# TRNG_ying.net
KiCad netlist of a schematic drawn in Altium Designer
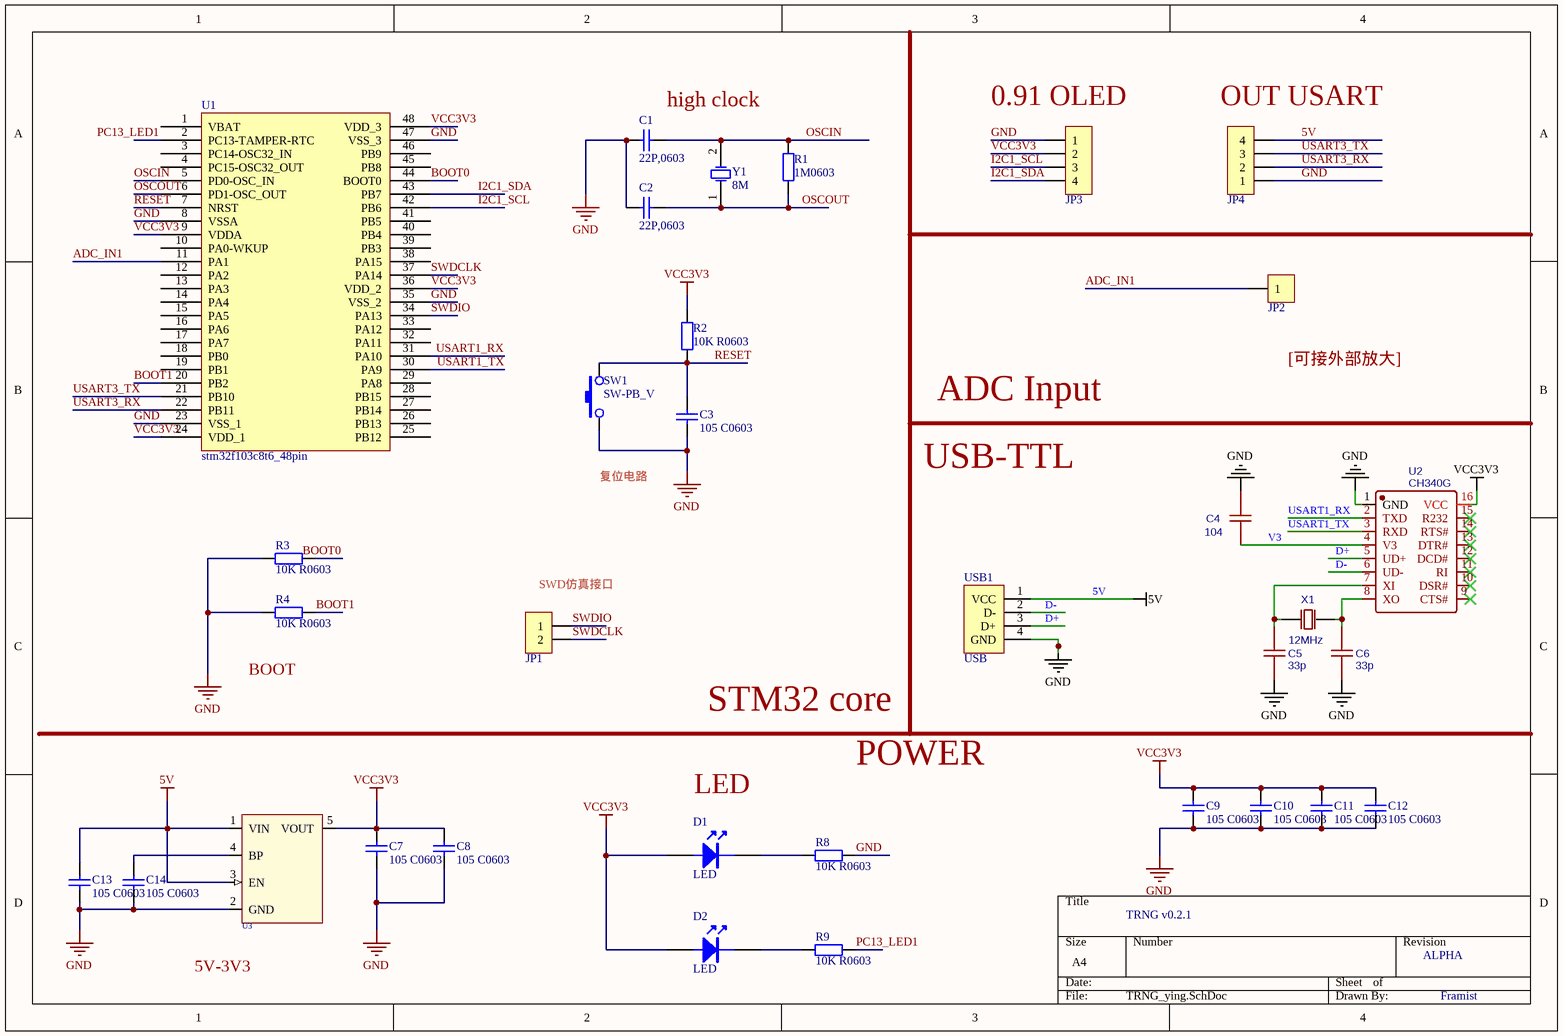
[diagram p0: TRNG_ying.SchDoc]

(export (version "E")
  (design (tool "Eeschema 10.0.6"))
  (components
    (comp (ref "C1")
      (value "22P,0603")
      (footprint "C 0603")
      (description "Capacitor")
      (fields (field (name "PUBLISHER") "Altium Limited"))
      (libsource (lib "STM32F103C8T6") (part "Cap"))
    )
    (comp (ref "C2")
      (value "22P,0603")
      (footprint "C 0603")
      (description "Capacitor")
      (fields (field (name "PUBLISHER") "Altium Limited"))
      (libsource (lib "STM32F103C8T6") (part "Cap"))
    )
    (comp (ref "C3")
      (value "105 C0603")
      (footprint "C 0603")
      (fields (field (name "PUBLISHER") "Altium Limited"))
      (libsource (lib "stm32原理图库") (part "Cap"))
    )
    (comp (ref "C4")
      (value "104")
      (footprint "C 0603")
      (fields
        (field (name "BOM_SUPPLIER PART") "C472790")
        (field (name "BOM_MANUFACTURER PART") "CL10C330JC81PNC")
        (field (name "CONTRIBUTOR") "LCSC")
      )
      (libsource (lib "altium-import") (part "root_1_104_"))
    )
    (comp (ref "C5")
      (value "33p")
      (footprint "C 0603")
      (fields
        (field (name "BOM_SUPPLIER PART") "C472790")
        (field (name "BOM_MANUFACTURER PART") "CL10C330JC81PNC")
        (field (name "CONTRIBUTOR") "LCSC")
      )
      (libsource (lib "altium-import") (part "root_1_33p_"))
    )
    (comp (ref "C6")
      (value "33p")
      (footprint "C 0603")
      (fields
        (field (name "BOM_SUPPLIER PART") "C472790")
        (field (name "BOM_MANUFACTURER PART") "CL10C330JC81PNC")
        (field (name "CONTRIBUTOR") "LCSC")
      )
      (libsource (lib "altium-import") (part "root_1_33p_"))
    )
    (comp (ref "C7")
      (value "105 C0603")
      (footprint "C 0603")
      (fields (field (name "PUBLISHER") "Altium Limited"))
      (libsource (lib "stm32原理图库") (part "Cap"))
    )
    (comp (ref "C8")
      (value "105 C0603")
      (footprint "C 0603")
      (fields (field (name "PUBLISHER") "Altium Limited"))
      (libsource (lib "stm32原理图库") (part "Cap"))
    )
    (comp (ref "C9")
      (value "105 C0603")
      (footprint "C 0603")
      (fields (field (name "PUBLISHER") "Altium Limited"))
      (libsource (lib "stm32原理图库") (part "Cap"))
    )
    (comp (ref "C10")
      (value "105 C0603")
      (footprint "C 0603")
      (fields (field (name "PUBLISHER") "Altium Limited"))
      (libsource (lib "stm32原理图库") (part "Cap"))
    )
    (comp (ref "C11")
      (value "105 C0603")
      (footprint "C 0603")
      (fields (field (name "PUBLISHER") "Altium Limited"))
      (libsource (lib "stm32原理图库") (part "Cap"))
    )
    (comp (ref "C12")
      (value "105 C0603")
      (footprint "C 0603")
      (fields (field (name "PUBLISHER") "Altium Limited"))
      (libsource (lib "stm32原理图库") (part "Cap"))
    )
    (comp (ref "C13")
      (value "105 C0603")
      (footprint "C 0603")
      (fields (field (name "PUBLISHER") "Altium Limited"))
      (libsource (lib "stm32原理图库") (part "Cap"))
    )
    (comp (ref "C14")
      (value "105 C0603")
      (footprint "C 0603")
      (fields (field (name "PUBLISHER") "Altium Limited"))
      (libsource (lib "stm32原理图库") (part "Cap"))
    )
    (comp (ref "D1") (value "LED") (footprint "LED 0805G") (libsource (lib "stm32原理图库") (part "LED")))
    (comp (ref "D2") (value "LED") (footprint "LED 0805G") (libsource (lib "stm32原理图库") (part "LED")))
    (comp (ref "JP1")
      (value "HDR-1X2")
      (footprint "HDR-1X2")
      (description "2P接插件")
      (fields (field (name "版权归属") "源创客"))
      (libsource (lib "接插件") (part "Header 2"))
    )
    (comp (ref "JP2")
      (value "HDR-1X1")
      (footprint "HDR-1X1")
      (description "1P接插件")
      (fields (field (name "版权归属") "源创客"))
      (libsource (lib "接插件") (part "Header 1"))
    )
    (comp (ref "JP3")
      (value "HDR-1X4")
      (footprint "HDR-1X4")
      (description "4P接插件")
      (fields (field (name "版权归属") "源创客"))
      (libsource (lib "接插件") (part "Header 4"))
    )
    (comp (ref "JP4")
      (value "HDR-1X4")
      (footprint "HDR-1X4")
      (description "4P接插件")
      (fields (field (name "版权归属") "源创客"))
      (libsource (lib "") (part "Header 4_1"))
    )
    (comp (ref "R1")
      (value "1M0603")
      (footprint "R 0603")
      (description "Resistor")
      (fields (field (name "PUBLISHER") "Altium Limited"))
      (libsource (lib "STM32F103C8T6") (part "Res2"))
    )
    (comp (ref "R2")
      (value "10K R0603")
      (footprint "R 0603")
      (fields (field (name "PUBLISHER") "Altium Limited"))
      (libsource (lib "") (part "Res2_1"))
    )
    (comp (ref "R3")
      (value "10K R0603")
      (footprint "R 0603")
      (fields (field (name "PUBLISHER") "Altium Limited"))
      (libsource (lib "") (part "Res2_2"))
    )
    (comp (ref "R4")
      (value "10K R0603")
      (footprint "R 0603")
      (fields (field (name "PUBLISHER") "Altium Limited"))
      (libsource (lib "stm32原理图库") (part "Res2"))
    )
    (comp (ref "R8")
      (value "10K R0603")
      (footprint "R 0603")
      (fields (field (name "PUBLISHER") "Altium Limited"))
      (libsource (lib "stm32原理图库") (part "Res2"))
    )
    (comp (ref "R9")
      (value "10K R0603")
      (footprint "R 0603")
      (fields (field (name "PUBLISHER") "Altium Limited"))
      (libsource (lib "stm32原理图库") (part "Res2"))
    )
    (comp (ref "SW1")
      (value "SW-PB_V")
      (footprint "TSW SMD-3*6*2.5")
      (libsource (lib "stm32原理图库") (part "SW-PB_V"))
    )
    (comp (ref "U1")
      (value "stm32f103c8t6_48pin")
      (footprint "TQFP48 7x7_L")
      (libsource (lib "STM32_Schlib") (part "stm32f103c8t6_48pin"))
    )
    (comp (ref "U2")
      (value "CH340G")
      (footprint "SOP16_M")
      (fields (field (name "BOM_SUPPLIER PART") "C14267"))
      (libsource (lib "altium-import") (part "root_0_CH340G_"))
    )
    (comp (ref "U3")
      (value "RT9193")
      (footprint "SOT23-5L")
      (fields (field (name "ICA_PARTNUM") "$$2191094$$RT9193-15CU5") (field (name "PART NUMBER") "TMP-13"))
      (libsource (lib "stm32原理图库") (part "RT9193X_5P"))
    )
    (comp (ref "USB1")
      (value "USB")
      (footprint "USB_A/P_A")
      (description "USB-A型公接口")
      (fields (field (name "版权归属") "源创客"))
      (libsource (lib "接口类") (part "USB-A/P"))
    )
    (comp (ref "X1")
      (value "12MHz")
      (footprint "XTAL-49S DIP")
      (fields
        (field (name "BOM_SUPPLIER PART") "C295065")
        (field (name "BOM_MANUFACTURER PART") "XSHEELNANF-12MHZ")
        (field (name "CONTRIBUTOR") "LCSC")
      )
      (libsource (lib "altium-import") (part "root_2_12MHz_"))
    )
    (comp (ref "Y1")
      (value "8M")
      (footprint "XTAL-49S DIP")
      (description "Crystal Oscillator")
      (fields (field (name "PUBLISHER") "Altium Limited"))
      (libsource (lib "STM32F103C8T6") (part "XTAL"))
    )
  )
  (nets
    (net (code "1") (name "/ADC_IN1") (class "Default")
      (node (ref "JP2") (pin "1") (pinfunction "1_1") (pintype "passive"))
      (node (ref "U1") (pin "11") (pinfunction "PA1_11") (pintype "passive"))
    )
    (net (code "2") (name "/BOOT0") (class "Default")
      (node (ref "R3") (pin "1") (pinfunction "1_1") (pintype "passive"))
      (node (ref "U1") (pin "44") (pinfunction "BOOT0_44") (pintype "passive"))
    )
    (net (code "3") (name "/BOOT1") (class "Default")
      (node (ref "R4") (pin "2") (pinfunction "2_2") (pintype "passive"))
      (node (ref "U1") (pin "20") (pinfunction "PB2_20") (pintype "passive"))
    )
    (net (code "4") (name "/D+") (class "Default")
      (node (ref "U2") (pin "5") (pinfunction "UD+_5") (pintype "passive"))
      (node (ref "USB1") (pin "3") (pinfunction "D+_3") (pintype "passive"))
    )
    (net (code "5") (name "/D-") (class "Default")
      (node (ref "U2") (pin "6") (pinfunction "UD-_6") (pintype "passive"))
      (node (ref "USB1") (pin "2") (pinfunction "D-_2") (pintype "passive"))
    )
    (net (code "6") (name "/I2C1_SCL") (class "Default")
      (node (ref "JP3") (pin "3") (pinfunction "3_3") (pintype "passive"))
      (node (ref "U1") (pin "42") (pinfunction "PB6_42") (pintype "passive"))
    )
    (net (code "7") (name "/I2C1_SDA") (class "Default")
      (node (ref "JP3") (pin "4") (pinfunction "4_4") (pintype "passive"))
      (node (ref "U1") (pin "43") (pinfunction "PB7_43") (pintype "passive"))
    )
    (net (code "8") (name "/OSCIN") (class "Default")
      (node (ref "C1") (pin "1") (pinfunction "1_1") (pintype "passive"))
      (node (ref "R1") (pin "2") (pinfunction "2_2") (pintype "passive"))
      (node (ref "U1") (pin "5") (pinfunction "PD0-OSC_IN_5") (pintype "passive"))
      (node (ref "Y1") (pin "2") (pinfunction "OSC2_2") (pintype "passive"))
    )
    (net (code "9") (name "/OSCOUT") (class "Default")
      (node (ref "C2") (pin "1") (pinfunction "1_1") (pintype "passive"))
      (node (ref "R1") (pin "1") (pinfunction "1_1") (pintype "passive"))
      (node (ref "U1") (pin "6") (pinfunction "PD1-OSC_OUT_6") (pintype "passive"))
      (node (ref "Y1") (pin "1") (pinfunction "OSC1_1") (pintype "passive"))
    )
    (net (code "10") (name "/PC13_LED1") (class "Default")
      (node (ref "R9") (pin "2") (pinfunction "2_2") (pintype "passive"))
      (node (ref "U1") (pin "2") (pinfunction "PC13-TAMPER-RTC_2") (pintype "passive"))
    )
    (net (code "11") (name "/RESET") (class "Default")
      (node (ref "C3") (pin "2") (pinfunction "2_2") (pintype "passive"))
      (node (ref "R2") (pin "1") (pinfunction "1_1") (pintype "passive"))
      (node (ref "SW1") (pin "2") (pinfunction "2_2") (pintype "passive"))
      (node (ref "U1") (pin "7") (pinfunction "NRST_7") (pintype "passive"))
    )
    (net (code "12") (name "/SWDCLK") (class "Default")
      (node (ref "JP1") (pin "2") (pinfunction "2_2") (pintype "passive"))
      (node (ref "U1") (pin "37") (pinfunction "PA14_37") (pintype "passive"))
    )
    (net (code "13") (name "/SWDIO") (class "Default")
      (node (ref "JP1") (pin "1") (pinfunction "1_1") (pintype "passive"))
      (node (ref "U1") (pin "34") (pinfunction "PA13_34") (pintype "passive"))
    )
    (net (code "14") (name "/USART1_RX") (class "Default")
      (node (ref "U1") (pin "31") (pinfunction "PA10_31") (pintype "passive"))
      (node (ref "U2") (pin "2") (pinfunction "TXD_2") (pintype "passive"))
    )
    (net (code "15") (name "/USART1_TX") (class "Default")
      (node (ref "U1") (pin "30") (pinfunction "PA9_30") (pintype "passive"))
      (node (ref "U2") (pin "3") (pinfunction "RXD_3") (pintype "passive"))
    )
    (net (code "16") (name "/USART3_RX") (class "Default")
      (node (ref "JP4") (pin "2") (pinfunction "2_2") (pintype "passive"))
      (node (ref "U1") (pin "22") (pinfunction "PB11_22") (pintype "passive"))
    )
    (net (code "17") (name "/USART3_TX") (class "Default")
      (node (ref "JP4") (pin "3") (pinfunction "3_3") (pintype "passive"))
      (node (ref "U1") (pin "21") (pinfunction "PB10_21") (pintype "passive"))
    )
    (net (code "18") (name "/V3") (class "Default")
      (node (ref "C4") (pin "1") (pinfunction "1_1") (pintype "passive"))
      (node (ref "U2") (pin "4") (pinfunction "V3_4") (pintype "passive"))
    )
    (net (code "19") (name "5V") (class "Default")
      (node (ref "C13") (pin "2") (pinfunction "2_2") (pintype "passive"))
      (node (ref "JP4") (pin "4") (pinfunction "4_4") (pintype "passive"))
      (node (ref "U3") (pin "1") (pinfunction "VIN_1") (pintype "power_in"))
      (node (ref "U3") (pin "3") (pinfunction "EN_3") (pintype "input"))
      (node (ref "USB1") (pin "1") (pinfunction "VCC_1") (pintype "passive"))
    )
    (net (code "20") (name "GND") (class "Default")
      (node (ref "C1") (pin "2") (pinfunction "2_2") (pintype "passive"))
      (node (ref "C10") (pin "1") (pinfunction "1_1") (pintype "passive"))
      (node (ref "C11") (pin "1") (pinfunction "1_1") (pintype "passive"))
      (node (ref "C12") (pin "1") (pinfunction "1_1") (pintype "passive"))
      (node (ref "C13") (pin "1") (pinfunction "1_1") (pintype "passive"))
      (node (ref "C14") (pin "1") (pinfunction "1_1") (pintype "passive"))
      (node (ref "C2") (pin "2") (pinfunction "2_2") (pintype "passive"))
      (node (ref "C3") (pin "1") (pinfunction "1_1") (pintype "passive"))
      (node (ref "C4") (pin "2") (pinfunction "2_2") (pintype "passive"))
      (node (ref "C5") (pin "1") (pinfunction "1_1") (pintype "passive"))
      (node (ref "C6") (pin "1") (pinfunction "1_1") (pintype "passive"))
      (node (ref "C7") (pin "1") (pinfunction "1_1") (pintype "passive"))
      (node (ref "C8") (pin "1") (pinfunction "1_1") (pintype "passive"))
      (node (ref "C9") (pin "1") (pinfunction "1_1") (pintype "passive"))
      (node (ref "JP3") (pin "1") (pinfunction "1_1") (pintype "passive"))
      (node (ref "JP4") (pin "1") (pinfunction "1_1") (pintype "passive"))
      (node (ref "R3") (pin "2") (pinfunction "2_2") (pintype "passive"))
      (node (ref "R4") (pin "1") (pinfunction "1_1") (pintype "passive"))
      (node (ref "R8") (pin "2") (pinfunction "2_2") (pintype "passive"))
      (node (ref "SW1") (pin "1") (pinfunction "1_1") (pintype "passive"))
      (node (ref "U1") (pin "23") (pinfunction "VSS_1_23") (pintype "passive"))
      (node (ref "U1") (pin "35") (pinfunction "VSS_2_35") (pintype "passive"))
      (node (ref "U1") (pin "47") (pinfunction "VSS_3_47") (pintype "passive"))
      (node (ref "U1") (pin "8") (pinfunction "VSSA_8") (pintype "passive"))
      (node (ref "U2") (pin "1") (pinfunction "GND_1") (pintype "passive"))
      (node (ref "U3") (pin "2") (pinfunction "GND_2") (pintype "power_in"))
      (node (ref "USB1") (pin "4") (pinfunction "GND_4") (pintype "passive"))
    )
    (net (code "21") (name "Net-(D1-Pad2)") (class "Default")
      (node (ref "D1") (pin "2") (pinfunction "2_2") (pintype "passive"))
      (node (ref "R8") (pin "1") (pinfunction "1_1") (pintype "passive"))
    )
    (net (code "22") (name "Net-(D2-Pad2)") (class "Default")
      (node (ref "D2") (pin "2") (pinfunction "2_2") (pintype "passive"))
      (node (ref "R9") (pin "1") (pinfunction "1_1") (pintype "passive"))
    )
    (net (code "23") (name "Net-(U2-XI)") (class "Default")
      (node (ref "C5") (pin "2") (pinfunction "2_2") (pintype "passive"))
      (node (ref "U2") (pin "7") (pinfunction "XI_7") (pintype "passive"))
      (node (ref "X1") (pin "2") (pinfunction "OSC2_2") (pintype "passive"))
    )
    (net (code "24") (name "Net-(U2-XO)") (class "Default")
      (node (ref "C6") (pin "2") (pinfunction "2_2") (pintype "passive"))
      (node (ref "U2") (pin "8") (pinfunction "XO_8") (pintype "passive"))
      (node (ref "X1") (pin "1") (pinfunction "OSC1_1") (pintype "passive"))
    )
    (net (code "25") (name "Net-(U3-BP)") (class "Default")
      (node (ref "C14") (pin "2") (pinfunction "2_2") (pintype "passive"))
      (node (ref "U3") (pin "4") (pinfunction "BP_4") (pintype "passive"))
    )
    (net (code "26") (name "VCC3V3") (class "Default")
      (node (ref "C10") (pin "2") (pinfunction "2_2") (pintype "passive"))
      (node (ref "C11") (pin "2") (pinfunction "2_2") (pintype "passive"))
      (node (ref "C12") (pin "2") (pinfunction "2_2") (pintype "passive"))
      (node (ref "C7") (pin "2") (pinfunction "2_2") (pintype "passive"))
      (node (ref "C8") (pin "2") (pinfunction "2_2") (pintype "passive"))
      (node (ref "C9") (pin "2") (pinfunction "2_2") (pintype "passive"))
      (node (ref "D1") (pin "1") (pinfunction "1_1") (pintype "passive"))
      (node (ref "D2") (pin "1") (pinfunction "1_1") (pintype "passive"))
      (node (ref "JP3") (pin "2") (pinfunction "2_2") (pintype "passive"))
      (node (ref "R2") (pin "2") (pinfunction "2_2") (pintype "passive"))
      (node (ref "U1") (pin "24") (pinfunction "VDD_1_24") (pintype "passive"))
      (node (ref "U1") (pin "36") (pinfunction "VDD_2_36") (pintype "passive"))
      (node (ref "U1") (pin "48") (pinfunction "VDD_3_48") (pintype "passive"))
      (node (ref "U1") (pin "9") (pinfunction "VDDA_9") (pintype "passive"))
      (node (ref "U2") (pin "16") (pinfunction "VCC_16") (pintype "passive"))
      (node (ref "U3") (pin "5") (pinfunction "VOUT_5") (pintype "power_in"))
    )
    (net (code "27") (name "unconnected-(U1-PA0-WKUP-Pad10)") (class "Default")
      (node (ref "U1") (pin "10") (pinfunction "PA0-WKUP_10") (pintype "passive"))
    )
    (net (code "28") (name "unconnected-(U1-PA2-Pad12)") (class "Default")
      (node (ref "U1") (pin "12") (pinfunction "PA2_12") (pintype "passive"))
    )
    (net (code "29") (name "unconnected-(U1-PA3-Pad13)") (class "Default")
      (node (ref "U1") (pin "13") (pinfunction "PA3_13") (pintype "passive"))
    )
    (net (code "30") (name "unconnected-(U1-PA4-Pad14)") (class "Default")
      (node (ref "U1") (pin "14") (pinfunction "PA4_14") (pintype "passive"))
    )
    (net (code "31") (name "unconnected-(U1-PA5-Pad15)") (class "Default")
      (node (ref "U1") (pin "15") (pinfunction "PA5_15") (pintype "passive"))
    )
    (net (code "32") (name "unconnected-(U1-PA6-Pad16)") (class "Default")
      (node (ref "U1") (pin "16") (pinfunction "PA6_16") (pintype "passive"))
    )
    (net (code "33") (name "unconnected-(U1-PA7-Pad17)") (class "Default")
      (node (ref "U1") (pin "17") (pinfunction "PA7_17") (pintype "passive"))
    )
    (net (code "34") (name "unconnected-(U1-PA8-Pad29)") (class "Default")
      (node (ref "U1") (pin "29") (pinfunction "PA8_29") (pintype "passive"))
    )
    (net (code "35") (name "unconnected-(U1-PA11-Pad32)") (class "Default")
      (node (ref "U1") (pin "32") (pinfunction "PA11_32") (pintype "passive"))
    )
    (net (code "36") (name "unconnected-(U1-PA12-Pad33)") (class "Default")
      (node (ref "U1") (pin "33") (pinfunction "PA12_33") (pintype "passive"))
    )
    (net (code "37") (name "unconnected-(U1-PA15-Pad38)") (class "Default")
      (node (ref "U1") (pin "38") (pinfunction "PA15_38") (pintype "passive"))
    )
    (net (code "38") (name "unconnected-(U1-PB0-Pad18)") (class "Default")
      (node (ref "U1") (pin "18") (pinfunction "PB0_18") (pintype "passive"))
    )
    (net (code "39") (name "unconnected-(U1-PB1-Pad19)") (class "Default")
      (node (ref "U1") (pin "19") (pinfunction "PB1_19") (pintype "passive"))
    )
    (net (code "40") (name "unconnected-(U1-PB3-Pad39)") (class "Default")
      (node (ref "U1") (pin "39") (pinfunction "PB3_39") (pintype "passive"))
    )
    (net (code "41") (name "unconnected-(U1-PB4-Pad40)") (class "Default")
      (node (ref "U1") (pin "40") (pinfunction "PB4_40") (pintype "passive"))
    )
    (net (code "42") (name "unconnected-(U1-PB5-Pad41)") (class "Default")
      (node (ref "U1") (pin "41") (pinfunction "PB5_41") (pintype "passive"))
    )
    (net (code "43") (name "unconnected-(U1-PB8-Pad45)") (class "Default")
      (node (ref "U1") (pin "45") (pinfunction "PB8_45") (pintype "passive"))
    )
    (net (code "44") (name "unconnected-(U1-PB9-Pad46)") (class "Default")
      (node (ref "U1") (pin "46") (pinfunction "PB9_46") (pintype "passive"))
    )
    (net (code "45") (name "unconnected-(U1-PB12-Pad25)") (class "Default")
      (node (ref "U1") (pin "25") (pinfunction "PB12_25") (pintype "passive"))
    )
    (net (code "46") (name "unconnected-(U1-PB13-Pad26)") (class "Default")
      (node (ref "U1") (pin "26") (pinfunction "PB13_26") (pintype "passive"))
    )
    (net (code "47") (name "unconnected-(U1-PB14-Pad27)") (class "Default")
      (node (ref "U1") (pin "27") (pinfunction "PB14_27") (pintype "passive"))
    )
    (net (code "48") (name "unconnected-(U1-PB15-Pad28)") (class "Default")
      (node (ref "U1") (pin "28") (pinfunction "PB15_28") (pintype "passive"))
    )
    (net (code "49") (name "unconnected-(U1-PC14-OSC32_IN-Pad3)") (class "Default")
      (node (ref "U1") (pin "3") (pinfunction "PC14-OSC32_IN_3") (pintype "passive"))
    )
    (net (code "50") (name "unconnected-(U1-PC15-OSC32_OUT-Pad4)") (class "Default")
      (node (ref "U1") (pin "4") (pinfunction "PC15-OSC32_OUT_4") (pintype "passive"))
    )
    (net (code "51") (name "unconnected-(U1-VBAT-Pad1)") (class "Default")
      (node (ref "U1") (pin "1") (pinfunction "VBAT_1") (pintype "passive"))
    )
    (net (code "52") (name "unconnected-(U2-CTS#-Pad9)") (class "Default")
      (node (ref "U2") (pin "9") (pinfunction "CTS#_9") (pintype "passive+no_connect"))
    )
    (net (code "53") (name "unconnected-(U2-DCD#-Pad12)") (class "Default")
      (node (ref "U2") (pin "12") (pinfunction "DCD#_12") (pintype "passive+no_connect"))
    )
    (net (code "54") (name "unconnected-(U2-DSR#-Pad10)") (class "Default")
      (node (ref "U2") (pin "10") (pinfunction "DSR#_10") (pintype "passive+no_connect"))
    )
    (net (code "55") (name "unconnected-(U2-DTR#-Pad13)") (class "Default")
      (node (ref "U2") (pin "13") (pinfunction "DTR#_13") (pintype "passive+no_connect"))
    )
    (net (code "56") (name "unconnected-(U2-R232-Pad15)") (class "Default")
      (node (ref "U2") (pin "15") (pinfunction "R232_15") (pintype "passive+no_connect"))
    )
    (net (code "57") (name "unconnected-(U2-RI-Pad11)") (class "Default")
      (node (ref "U2") (pin "11") (pinfunction "RI_11") (pintype "passive+no_connect"))
    )
    (net (code "58") (name "unconnected-(U2-RTS#-Pad14)") (class "Default")
      (node (ref "U2") (pin "14") (pinfunction "RTS#_14") (pintype "passive+no_connect"))
    )
  )
)
